# ground_logic_thing_v1.net
KiCad netlist of a schematic drawn in EAGLE
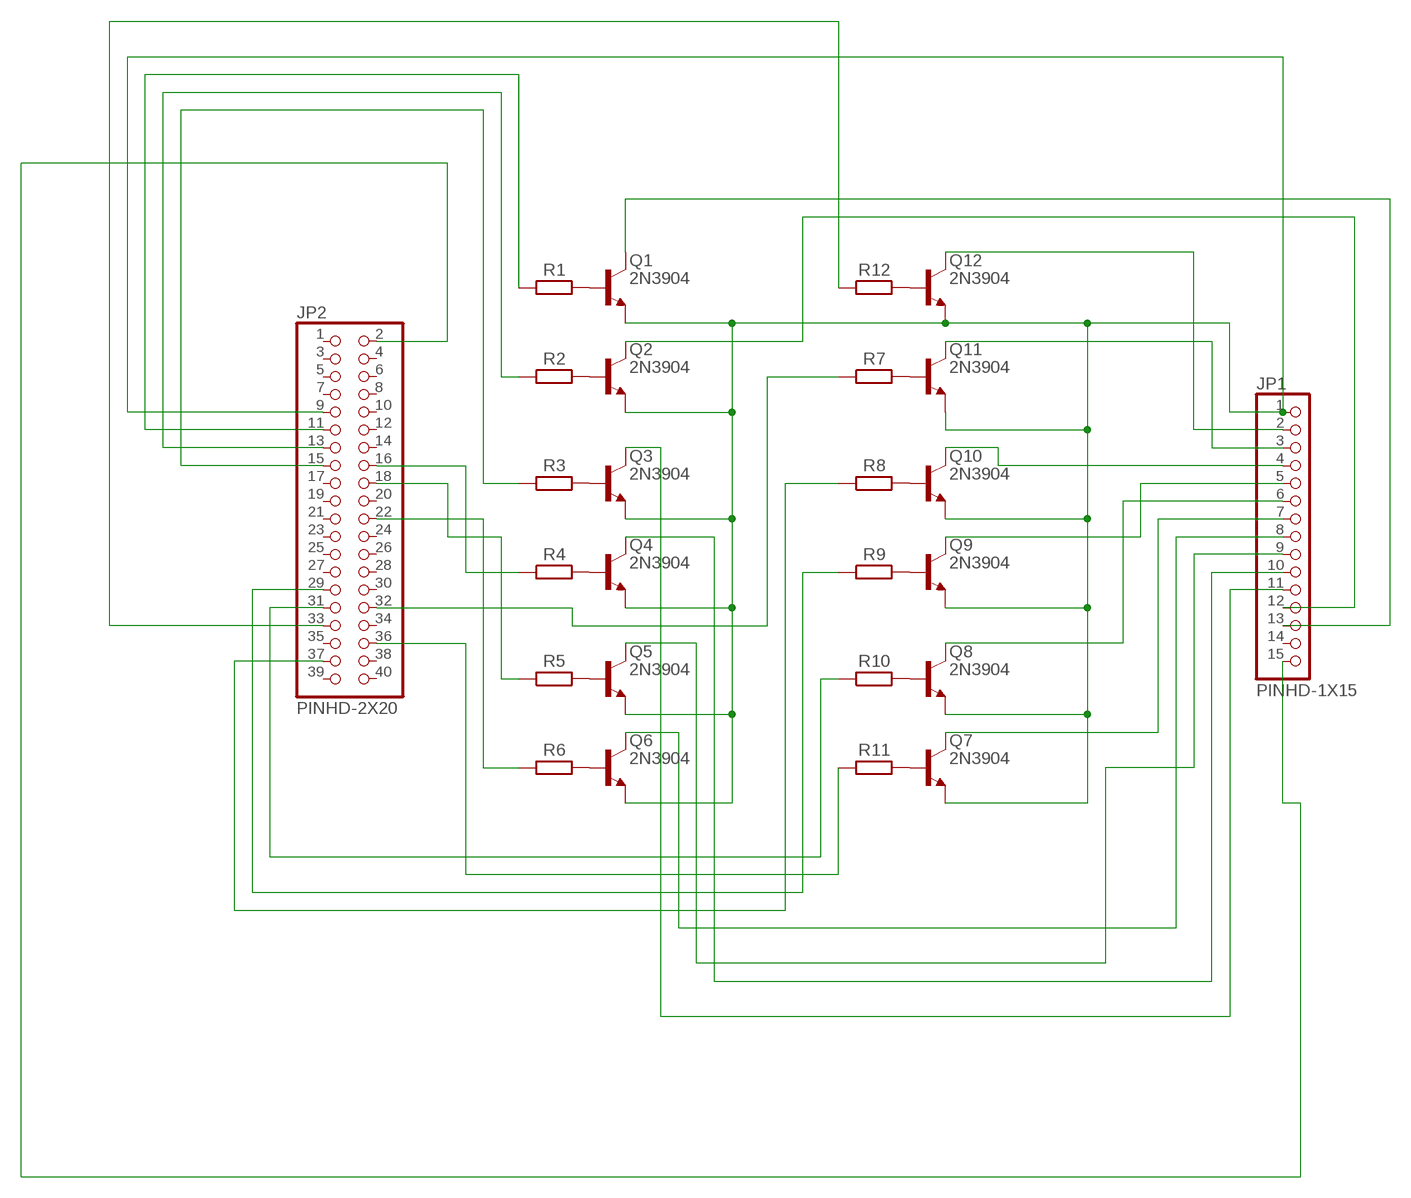
[diagram p0: schematic, sheet 1]

(export (version "E")
  (design (tool "Eeschema 10.0.6"))
  (components
    (comp (ref "JP1")
      (value "PINHD-1X15")
      (footprint "eagle-import:1X15")
      (libsource (lib "eagle-import") (part "PINHD-1X15"))
    )
    (comp (ref "JP2")
      (value "PINHD-2X20")
      (footprint "eagle-import:2X20")
      (libsource (lib "eagle-import") (part "PINHD-2X20"))
    )
    (comp (ref "Q1")
      (value "2N3904")
      (footprint "eagle-import:TO92")
      (libsource (lib "eagle-import") (part "NPN__TO922N3904"))
    )
    (comp (ref "Q2")
      (value "2N3904")
      (footprint "eagle-import:TO92")
      (libsource (lib "eagle-import") (part "NPN__TO922N3904"))
    )
    (comp (ref "Q3")
      (value "2N3904")
      (footprint "eagle-import:TO92")
      (libsource (lib "eagle-import") (part "NPN__TO922N3904"))
    )
    (comp (ref "Q4")
      (value "2N3904")
      (footprint "eagle-import:TO92")
      (libsource (lib "eagle-import") (part "NPN__TO922N3904"))
    )
    (comp (ref "Q5")
      (value "2N3904")
      (footprint "eagle-import:TO92")
      (libsource (lib "eagle-import") (part "NPN__TO922N3904"))
    )
    (comp (ref "Q6")
      (value "2N3904")
      (footprint "eagle-import:TO92")
      (libsource (lib "eagle-import") (part "NPN__TO922N3904"))
    )
    (comp (ref "Q7")
      (value "2N3904")
      (footprint "eagle-import:TO92")
      (libsource (lib "eagle-import") (part "NPN__TO922N3904"))
    )
    (comp (ref "Q8")
      (value "2N3904")
      (footprint "eagle-import:TO92")
      (libsource (lib "eagle-import") (part "NPN__TO922N3904"))
    )
    (comp (ref "Q9")
      (value "2N3904")
      (footprint "eagle-import:TO92")
      (libsource (lib "eagle-import") (part "NPN__TO922N3904"))
    )
    (comp (ref "Q10")
      (value "2N3904")
      (footprint "eagle-import:TO92")
      (libsource (lib "eagle-import") (part "NPN__TO922N3904"))
    )
    (comp (ref "Q11")
      (value "2N3904")
      (footprint "eagle-import:TO92")
      (libsource (lib "eagle-import") (part "NPN__TO922N3904"))
    )
    (comp (ref "Q12")
      (value "2N3904")
      (footprint "eagle-import:TO92")
      (libsource (lib "eagle-import") (part "NPN__TO922N3904"))
    )
    (comp (ref "R1")
      (value "R_AXIAL-7.2MM-PITCH")
      (footprint "eagle-import:RESAD724W46L381D178B")
      (libsource (lib "eagle-import") (part "RAXIAL-7.2MM-PITCH_"))
    )
    (comp (ref "R2")
      (value "R_AXIAL-7.2MM-PITCH")
      (footprint "eagle-import:RESAD724W46L381D178B")
      (libsource (lib "eagle-import") (part "RAXIAL-7.2MM-PITCH_"))
    )
    (comp (ref "R3")
      (value "R_AXIAL-7.2MM-PITCH")
      (footprint "eagle-import:RESAD724W46L381D178B")
      (libsource (lib "eagle-import") (part "RAXIAL-7.2MM-PITCH_"))
    )
    (comp (ref "R4")
      (value "R_AXIAL-7.2MM-PITCH")
      (footprint "eagle-import:RESAD724W46L381D178B")
      (libsource (lib "eagle-import") (part "RAXIAL-7.2MM-PITCH_"))
    )
    (comp (ref "R5")
      (value "R_AXIAL-7.2MM-PITCH")
      (footprint "eagle-import:RESAD724W46L381D178B")
      (libsource (lib "eagle-import") (part "RAXIAL-7.2MM-PITCH_"))
    )
    (comp (ref "R6")
      (value "R_AXIAL-7.2MM-PITCH")
      (footprint "eagle-import:RESAD724W46L381D178B")
      (libsource (lib "eagle-import") (part "RAXIAL-7.2MM-PITCH_"))
    )
    (comp (ref "R7")
      (value "R_AXIAL-7.2MM-PITCH")
      (footprint "eagle-import:RESAD724W46L381D178B")
      (libsource (lib "eagle-import") (part "RAXIAL-7.2MM-PITCH_"))
    )
    (comp (ref "R8")
      (value "R_AXIAL-7.2MM-PITCH")
      (footprint "eagle-import:RESAD724W46L381D178B")
      (libsource (lib "eagle-import") (part "RAXIAL-7.2MM-PITCH_"))
    )
    (comp (ref "R9")
      (value "R_AXIAL-7.2MM-PITCH")
      (footprint "eagle-import:RESAD724W46L381D178B")
      (libsource (lib "eagle-import") (part "RAXIAL-7.2MM-PITCH_"))
    )
    (comp (ref "R10")
      (value "R_AXIAL-7.2MM-PITCH")
      (footprint "eagle-import:RESAD724W46L381D178B")
      (libsource (lib "eagle-import") (part "RAXIAL-7.2MM-PITCH_"))
    )
    (comp (ref "R11")
      (value "R_AXIAL-7.2MM-PITCH")
      (footprint "eagle-import:RESAD724W46L381D178B")
      (libsource (lib "eagle-import") (part "RAXIAL-7.2MM-PITCH_"))
    )
    (comp (ref "R12")
      (value "R_AXIAL-7.2MM-PITCH")
      (footprint "eagle-import:RESAD724W46L381D178B")
      (libsource (lib "eagle-import") (part "RAXIAL-7.2MM-PITCH_"))
    )
  )
  (nets
    (net (code "1") (name "Net-(JP1-Pad15)") (class "Default")
      (node (ref "JP1") (pin "15") (pinfunction "15_15") (pintype "passive"))
      (node (ref "JP2") (pin "2") (pinfunction "2_2") (pintype "passive"))
    )
    (net (code "2") (name "Net-(JP2-Pad11)") (class "Default")
      (node (ref "JP2") (pin "11") (pinfunction "11_11") (pintype "passive"))
      (node (ref "R1") (pin "1") (pinfunction "1_1") (pintype "passive"))
    )
    (net (code "3") (name "Net-(JP2-Pad13)") (class "Default")
      (node (ref "JP2") (pin "13") (pinfunction "13_13") (pintype "passive"))
      (node (ref "R2") (pin "1") (pinfunction "1_1") (pintype "passive"))
    )
    (net (code "4") (name "Net-(JP2-Pad15)") (class "Default")
      (node (ref "JP2") (pin "15") (pinfunction "15_15") (pintype "passive"))
      (node (ref "R3") (pin "1") (pinfunction "1_1") (pintype "passive"))
    )
    (net (code "5") (name "Net-(JP2-Pad16)") (class "Default")
      (node (ref "JP2") (pin "16") (pinfunction "16_16") (pintype "passive"))
      (node (ref "R4") (pin "1") (pinfunction "1_1") (pintype "passive"))
    )
    (net (code "6") (name "Net-(JP2-Pad18)") (class "Default")
      (node (ref "JP2") (pin "18") (pinfunction "18_18") (pintype "passive"))
      (node (ref "R5") (pin "1") (pinfunction "1_1") (pintype "passive"))
    )
    (net (code "7") (name "Net-(JP2-Pad22)") (class "Default")
      (node (ref "JP2") (pin "22") (pinfunction "22_22") (pintype "passive"))
      (node (ref "R6") (pin "1") (pinfunction "1_1") (pintype "passive"))
    )
    (net (code "8") (name "Net-(JP2-Pad29)") (class "Default")
      (node (ref "JP2") (pin "29") (pinfunction "29_29") (pintype "passive"))
      (node (ref "R9") (pin "1") (pinfunction "1_1") (pintype "passive"))
    )
    (net (code "9") (name "Net-(JP2-Pad31)") (class "Default")
      (node (ref "JP2") (pin "31") (pinfunction "31_31") (pintype "passive"))
      (node (ref "R10") (pin "1") (pinfunction "1_1") (pintype "passive"))
    )
    (net (code "10") (name "Net-(JP2-Pad32)") (class "Default")
      (node (ref "JP2") (pin "32") (pinfunction "32_32") (pintype "passive"))
      (node (ref "R7") (pin "1") (pinfunction "1_1") (pintype "passive"))
    )
    (net (code "11") (name "Net-(JP2-Pad33)") (class "Default")
      (node (ref "JP2") (pin "33") (pinfunction "33_33") (pintype "passive"))
      (node (ref "R12") (pin "1") (pinfunction "1_1") (pintype "passive"))
    )
    (net (code "12") (name "Net-(JP2-Pad36)") (class "Default")
      (node (ref "JP2") (pin "36") (pinfunction "36_36") (pintype "passive"))
      (node (ref "R11") (pin "1") (pinfunction "1_1") (pintype "passive"))
    )
    (net (code "13") (name "Net-(JP2-Pad37)") (class "Default")
      (node (ref "JP2") (pin "37") (pinfunction "37_37") (pintype "passive"))
      (node (ref "R8") (pin "1") (pinfunction "1_1") (pintype "passive"))
    )
    (net (code "14") (name "Net-(Q1-B)") (class "Default")
      (node (ref "Q1") (pin "2") (pinfunction "B_2") (pintype "passive"))
      (node (ref "R1") (pin "2") (pinfunction "2_2") (pintype "passive"))
    )
    (net (code "15") (name "Net-(Q1-C)") (class "Default")
      (node (ref "JP1") (pin "13") (pinfunction "13_13") (pintype "passive"))
      (node (ref "Q1") (pin "3") (pinfunction "C_3") (pintype "passive"))
    )
    (net (code "16") (name "Net-(Q1-E)") (class "Default")
      (node (ref "JP1") (pin "1") (pinfunction "1_1") (pintype "passive"))
      (node (ref "JP2") (pin "9") (pinfunction "9_9") (pintype "passive"))
      (node (ref "Q1") (pin "1") (pinfunction "E_1") (pintype "passive"))
      (node (ref "Q10") (pin "1") (pinfunction "E_1") (pintype "passive"))
      (node (ref "Q11") (pin "1") (pinfunction "E_1") (pintype "passive"))
      (node (ref "Q12") (pin "1") (pinfunction "E_1") (pintype "passive"))
      (node (ref "Q2") (pin "1") (pinfunction "E_1") (pintype "passive"))
      (node (ref "Q3") (pin "1") (pinfunction "E_1") (pintype "passive"))
      (node (ref "Q4") (pin "1") (pinfunction "E_1") (pintype "passive"))
      (node (ref "Q5") (pin "1") (pinfunction "E_1") (pintype "passive"))
      (node (ref "Q6") (pin "1") (pinfunction "E_1") (pintype "passive"))
      (node (ref "Q7") (pin "1") (pinfunction "E_1") (pintype "passive"))
      (node (ref "Q8") (pin "1") (pinfunction "E_1") (pintype "passive"))
      (node (ref "Q9") (pin "1") (pinfunction "E_1") (pintype "passive"))
    )
    (net (code "17") (name "Net-(Q2-B)") (class "Default")
      (node (ref "Q2") (pin "2") (pinfunction "B_2") (pintype "passive"))
      (node (ref "R2") (pin "2") (pinfunction "2_2") (pintype "passive"))
    )
    (net (code "18") (name "Net-(Q2-C)") (class "Default")
      (node (ref "JP1") (pin "12") (pinfunction "12_12") (pintype "passive"))
      (node (ref "Q2") (pin "3") (pinfunction "C_3") (pintype "passive"))
    )
    (net (code "19") (name "Net-(Q3-B)") (class "Default")
      (node (ref "Q3") (pin "2") (pinfunction "B_2") (pintype "passive"))
      (node (ref "R3") (pin "2") (pinfunction "2_2") (pintype "passive"))
    )
    (net (code "20") (name "Net-(Q3-C)") (class "Default")
      (node (ref "JP1") (pin "11") (pinfunction "11_11") (pintype "passive"))
      (node (ref "Q3") (pin "3") (pinfunction "C_3") (pintype "passive"))
    )
    (net (code "21") (name "Net-(Q4-B)") (class "Default")
      (node (ref "Q4") (pin "2") (pinfunction "B_2") (pintype "passive"))
      (node (ref "R4") (pin "2") (pinfunction "2_2") (pintype "passive"))
    )
    (net (code "22") (name "Net-(Q4-C)") (class "Default")
      (node (ref "JP1") (pin "10") (pinfunction "10_10") (pintype "passive"))
      (node (ref "Q4") (pin "3") (pinfunction "C_3") (pintype "passive"))
    )
    (net (code "23") (name "Net-(Q5-B)") (class "Default")
      (node (ref "Q5") (pin "2") (pinfunction "B_2") (pintype "passive"))
      (node (ref "R5") (pin "2") (pinfunction "2_2") (pintype "passive"))
    )
    (net (code "24") (name "Net-(Q5-C)") (class "Default")
      (node (ref "JP1") (pin "9") (pinfunction "9_9") (pintype "passive"))
      (node (ref "Q5") (pin "3") (pinfunction "C_3") (pintype "passive"))
    )
    (net (code "25") (name "Net-(Q6-B)") (class "Default")
      (node (ref "Q6") (pin "2") (pinfunction "B_2") (pintype "passive"))
      (node (ref "R6") (pin "2") (pinfunction "2_2") (pintype "passive"))
    )
    (net (code "26") (name "Net-(Q6-C)") (class "Default")
      (node (ref "JP1") (pin "8") (pinfunction "8_8") (pintype "passive"))
      (node (ref "Q6") (pin "3") (pinfunction "C_3") (pintype "passive"))
    )
    (net (code "27") (name "Net-(Q7-B)") (class "Default")
      (node (ref "Q7") (pin "2") (pinfunction "B_2") (pintype "passive"))
      (node (ref "R11") (pin "2") (pinfunction "2_2") (pintype "passive"))
    )
    (net (code "28") (name "Net-(Q7-C)") (class "Default")
      (node (ref "JP1") (pin "7") (pinfunction "7_7") (pintype "passive"))
      (node (ref "Q7") (pin "3") (pinfunction "C_3") (pintype "passive"))
    )
    (net (code "29") (name "Net-(Q8-B)") (class "Default")
      (node (ref "Q8") (pin "2") (pinfunction "B_2") (pintype "passive"))
      (node (ref "R10") (pin "2") (pinfunction "2_2") (pintype "passive"))
    )
    (net (code "30") (name "Net-(Q8-C)") (class "Default")
      (node (ref "JP1") (pin "6") (pinfunction "6_6") (pintype "passive"))
      (node (ref "Q8") (pin "3") (pinfunction "C_3") (pintype "passive"))
    )
    (net (code "31") (name "Net-(Q9-B)") (class "Default")
      (node (ref "Q9") (pin "2") (pinfunction "B_2") (pintype "passive"))
      (node (ref "R9") (pin "2") (pinfunction "2_2") (pintype "passive"))
    )
    (net (code "32") (name "Net-(Q9-C)") (class "Default")
      (node (ref "JP1") (pin "5") (pinfunction "5_5") (pintype "passive"))
      (node (ref "Q9") (pin "3") (pinfunction "C_3") (pintype "passive"))
    )
    (net (code "33") (name "Net-(Q10-B)") (class "Default")
      (node (ref "Q10") (pin "2") (pinfunction "B_2") (pintype "passive"))
      (node (ref "R8") (pin "2") (pinfunction "2_2") (pintype "passive"))
    )
    (net (code "34") (name "Net-(Q10-C)") (class "Default")
      (node (ref "JP1") (pin "4") (pinfunction "4_4") (pintype "passive"))
      (node (ref "Q10") (pin "3") (pinfunction "C_3") (pintype "passive"))
    )
    (net (code "35") (name "Net-(Q11-B)") (class "Default")
      (node (ref "Q11") (pin "2") (pinfunction "B_2") (pintype "passive"))
      (node (ref "R7") (pin "2") (pinfunction "2_2") (pintype "passive"))
    )
    (net (code "36") (name "Net-(Q11-C)") (class "Default")
      (node (ref "JP1") (pin "3") (pinfunction "3_3") (pintype "passive"))
      (node (ref "Q11") (pin "3") (pinfunction "C_3") (pintype "passive"))
    )
    (net (code "37") (name "Net-(Q12-B)") (class "Default")
      (node (ref "Q12") (pin "2") (pinfunction "B_2") (pintype "passive"))
      (node (ref "R12") (pin "2") (pinfunction "2_2") (pintype "passive"))
    )
    (net (code "38") (name "Net-(Q12-C)") (class "Default")
      (node (ref "JP1") (pin "2") (pinfunction "2_2") (pintype "passive"))
      (node (ref "Q12") (pin "3") (pinfunction "C_3") (pintype "passive"))
    )
    (net (code "39") (name "unconnected-(JP1-Pad14)") (class "Default")
      (node (ref "JP1") (pin "14") (pinfunction "14_14") (pintype "passive"))
    )
    (net (code "40") (name "unconnected-(JP2-Pad1)") (class "Default")
      (node (ref "JP2") (pin "1") (pinfunction "1_1") (pintype "passive"))
    )
    (net (code "41") (name "unconnected-(JP2-Pad3)") (class "Default")
      (node (ref "JP2") (pin "3") (pinfunction "3_3") (pintype "passive"))
    )
    (net (code "42") (name "unconnected-(JP2-Pad4)") (class "Default")
      (node (ref "JP2") (pin "4") (pinfunction "4_4") (pintype "passive"))
    )
    (net (code "43") (name "unconnected-(JP2-Pad5)") (class "Default")
      (node (ref "JP2") (pin "5") (pinfunction "5_5") (pintype "passive"))
    )
    (net (code "44") (name "unconnected-(JP2-Pad6)") (class "Default")
      (node (ref "JP2") (pin "6") (pinfunction "6_6") (pintype "passive"))
    )
    (net (code "45") (name "unconnected-(JP2-Pad7)") (class "Default")
      (node (ref "JP2") (pin "7") (pinfunction "7_7") (pintype "passive"))
    )
    (net (code "46") (name "unconnected-(JP2-Pad8)") (class "Default")
      (node (ref "JP2") (pin "8") (pinfunction "8_8") (pintype "passive"))
    )
    (net (code "47") (name "unconnected-(JP2-Pad10)") (class "Default")
      (node (ref "JP2") (pin "10") (pinfunction "10_10") (pintype "passive"))
    )
    (net (code "48") (name "unconnected-(JP2-Pad12)") (class "Default")
      (node (ref "JP2") (pin "12") (pinfunction "12_12") (pintype "passive"))
    )
    (net (code "49") (name "unconnected-(JP2-Pad14)") (class "Default")
      (node (ref "JP2") (pin "14") (pinfunction "14_14") (pintype "passive"))
    )
    (net (code "50") (name "unconnected-(JP2-Pad17)") (class "Default")
      (node (ref "JP2") (pin "17") (pinfunction "17_17") (pintype "passive"))
    )
    (net (code "51") (name "unconnected-(JP2-Pad19)") (class "Default")
      (node (ref "JP2") (pin "19") (pinfunction "19_19") (pintype "passive"))
    )
    (net (code "52") (name "unconnected-(JP2-Pad20)") (class "Default")
      (node (ref "JP2") (pin "20") (pinfunction "20_20") (pintype "passive"))
    )
    (net (code "53") (name "unconnected-(JP2-Pad21)") (class "Default")
      (node (ref "JP2") (pin "21") (pinfunction "21_21") (pintype "passive"))
    )
    (net (code "54") (name "unconnected-(JP2-Pad23)") (class "Default")
      (node (ref "JP2") (pin "23") (pinfunction "23_23") (pintype "passive"))
    )
    (net (code "55") (name "unconnected-(JP2-Pad24)") (class "Default")
      (node (ref "JP2") (pin "24") (pinfunction "24_24") (pintype "passive"))
    )
    (net (code "56") (name "unconnected-(JP2-Pad25)") (class "Default")
      (node (ref "JP2") (pin "25") (pinfunction "25_25") (pintype "passive"))
    )
    (net (code "57") (name "unconnected-(JP2-Pad26)") (class "Default")
      (node (ref "JP2") (pin "26") (pinfunction "26_26") (pintype "passive"))
    )
    (net (code "58") (name "unconnected-(JP2-Pad27)") (class "Default")
      (node (ref "JP2") (pin "27") (pinfunction "27_27") (pintype "passive"))
    )
    (net (code "59") (name "unconnected-(JP2-Pad28)") (class "Default")
      (node (ref "JP2") (pin "28") (pinfunction "28_28") (pintype "passive"))
    )
    (net (code "60") (name "unconnected-(JP2-Pad30)") (class "Default")
      (node (ref "JP2") (pin "30") (pinfunction "30_30") (pintype "passive"))
    )
    (net (code "61") (name "unconnected-(JP2-Pad34)") (class "Default")
      (node (ref "JP2") (pin "34") (pinfunction "34_34") (pintype "passive"))
    )
    (net (code "62") (name "unconnected-(JP2-Pad35)") (class "Default")
      (node (ref "JP2") (pin "35") (pinfunction "35_35") (pintype "passive"))
    )
    (net (code "63") (name "unconnected-(JP2-Pad38)") (class "Default")
      (node (ref "JP2") (pin "38") (pinfunction "38_38") (pintype "passive"))
    )
    (net (code "64") (name "unconnected-(JP2-Pad39)") (class "Default")
      (node (ref "JP2") (pin "39") (pinfunction "39_39") (pintype "passive"))
    )
    (net (code "65") (name "unconnected-(JP2-Pad40)") (class "Default")
      (node (ref "JP2") (pin "40") (pinfunction "40_40") (pintype "passive"))
    )
  )
)
